# JTag2SWD.net
KiCad netlist of a schematic drawn in Altium Designer
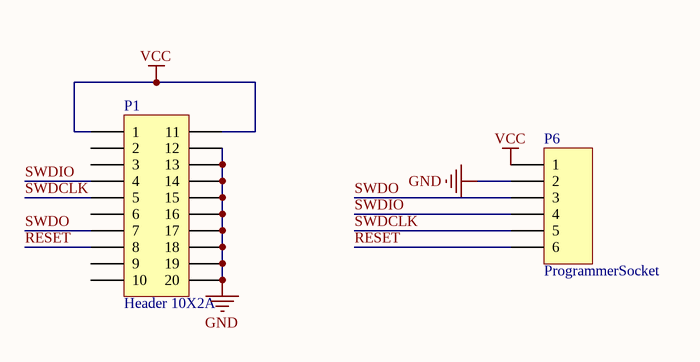
[diagram p0: JTag2SWD.SchDoc]

(export (version "E")
  (design (tool "Eeschema 10.0.6"))
  (components
    (comp (ref "P1")
      (value "Header 10X2A")
      (footprint "HDR2X10_CEN")
      (description "Header, 10-Pin, Dual row")
      (fields (field (name "PUBLISHER") "Altium Limited"))
      (libsource (lib "Miscellaneous Connectors") (part "Header 10X2A"))
    )
    (comp (ref "P6")
      (value "ProgrammerSocket")
      (footprint "HDR1X6")
      (description "Header, 6-Pin")
      (fields (field (name "PUBLISHER") "Altium Limited"))
      (libsource (lib "Miscellaneous Connectors") (part "Header 6"))
    )
  )
  (nets
    (net (code "1") (name "/RESET") (class "Default")
      (node (ref "P1") (pin "8") (pinfunction "8_8") (pintype "passive"))
      (node (ref "P6") (pin "6") (pinfunction "6_6") (pintype "passive"))
    )
    (net (code "2") (name "/SWDCLK") (class "Default")
      (node (ref "P1") (pin "5") (pinfunction "5_5") (pintype "passive"))
      (node (ref "P6") (pin "5") (pinfunction "5_5") (pintype "passive"))
    )
    (net (code "3") (name "/SWDIO") (class "Default")
      (node (ref "P1") (pin "4") (pinfunction "4_4") (pintype "passive"))
      (node (ref "P6") (pin "4") (pinfunction "4_4") (pintype "passive"))
    )
    (net (code "4") (name "/SWDO") (class "Default")
      (node (ref "P1") (pin "7") (pinfunction "7_7") (pintype "passive"))
      (node (ref "P6") (pin "3") (pinfunction "3_3") (pintype "passive"))
    )
    (net (code "5") (name "GND") (class "Default")
      (node (ref "P1") (pin "12") (pinfunction "12_12") (pintype "passive"))
      (node (ref "P1") (pin "13") (pinfunction "13_13") (pintype "passive"))
      (node (ref "P1") (pin "14") (pinfunction "14_14") (pintype "passive"))
      (node (ref "P1") (pin "15") (pinfunction "15_15") (pintype "passive"))
      (node (ref "P1") (pin "16") (pinfunction "16_16") (pintype "passive"))
      (node (ref "P1") (pin "17") (pinfunction "17_17") (pintype "passive"))
      (node (ref "P1") (pin "18") (pinfunction "18_18") (pintype "passive"))
      (node (ref "P1") (pin "19") (pinfunction "19_19") (pintype "passive"))
      (node (ref "P1") (pin "20") (pinfunction "20_20") (pintype "passive"))
      (node (ref "P6") (pin "2") (pinfunction "2_2") (pintype "passive"))
    )
    (net (code "6") (name "VCC") (class "Default")
      (node (ref "P1") (pin "1") (pinfunction "1_1") (pintype "passive"))
      (node (ref "P1") (pin "11") (pinfunction "11_11") (pintype "passive"))
      (node (ref "P6") (pin "1") (pinfunction "1_1") (pintype "passive"))
    )
    (net (code "7") (name "unconnected-(P1-Pad2)") (class "Default")
      (node (ref "P1") (pin "2") (pinfunction "2_2") (pintype "passive"))
    )
    (net (code "8") (name "unconnected-(P1-Pad3)") (class "Default")
      (node (ref "P1") (pin "3") (pinfunction "3_3") (pintype "passive"))
    )
    (net (code "9") (name "unconnected-(P1-Pad6)") (class "Default")
      (node (ref "P1") (pin "6") (pinfunction "6_6") (pintype "passive"))
    )
    (net (code "10") (name "unconnected-(P1-Pad9)") (class "Default")
      (node (ref "P1") (pin "9") (pinfunction "9_9") (pintype "passive"))
    )
    (net (code "11") (name "unconnected-(P1-Pad10)") (class "Default")
      (node (ref "P1") (pin "10") (pinfunction "10_10") (pintype "passive"))
    )
  )
)
